# door_sensor.net
KiCad netlist of a schematic drawn in EAGLE
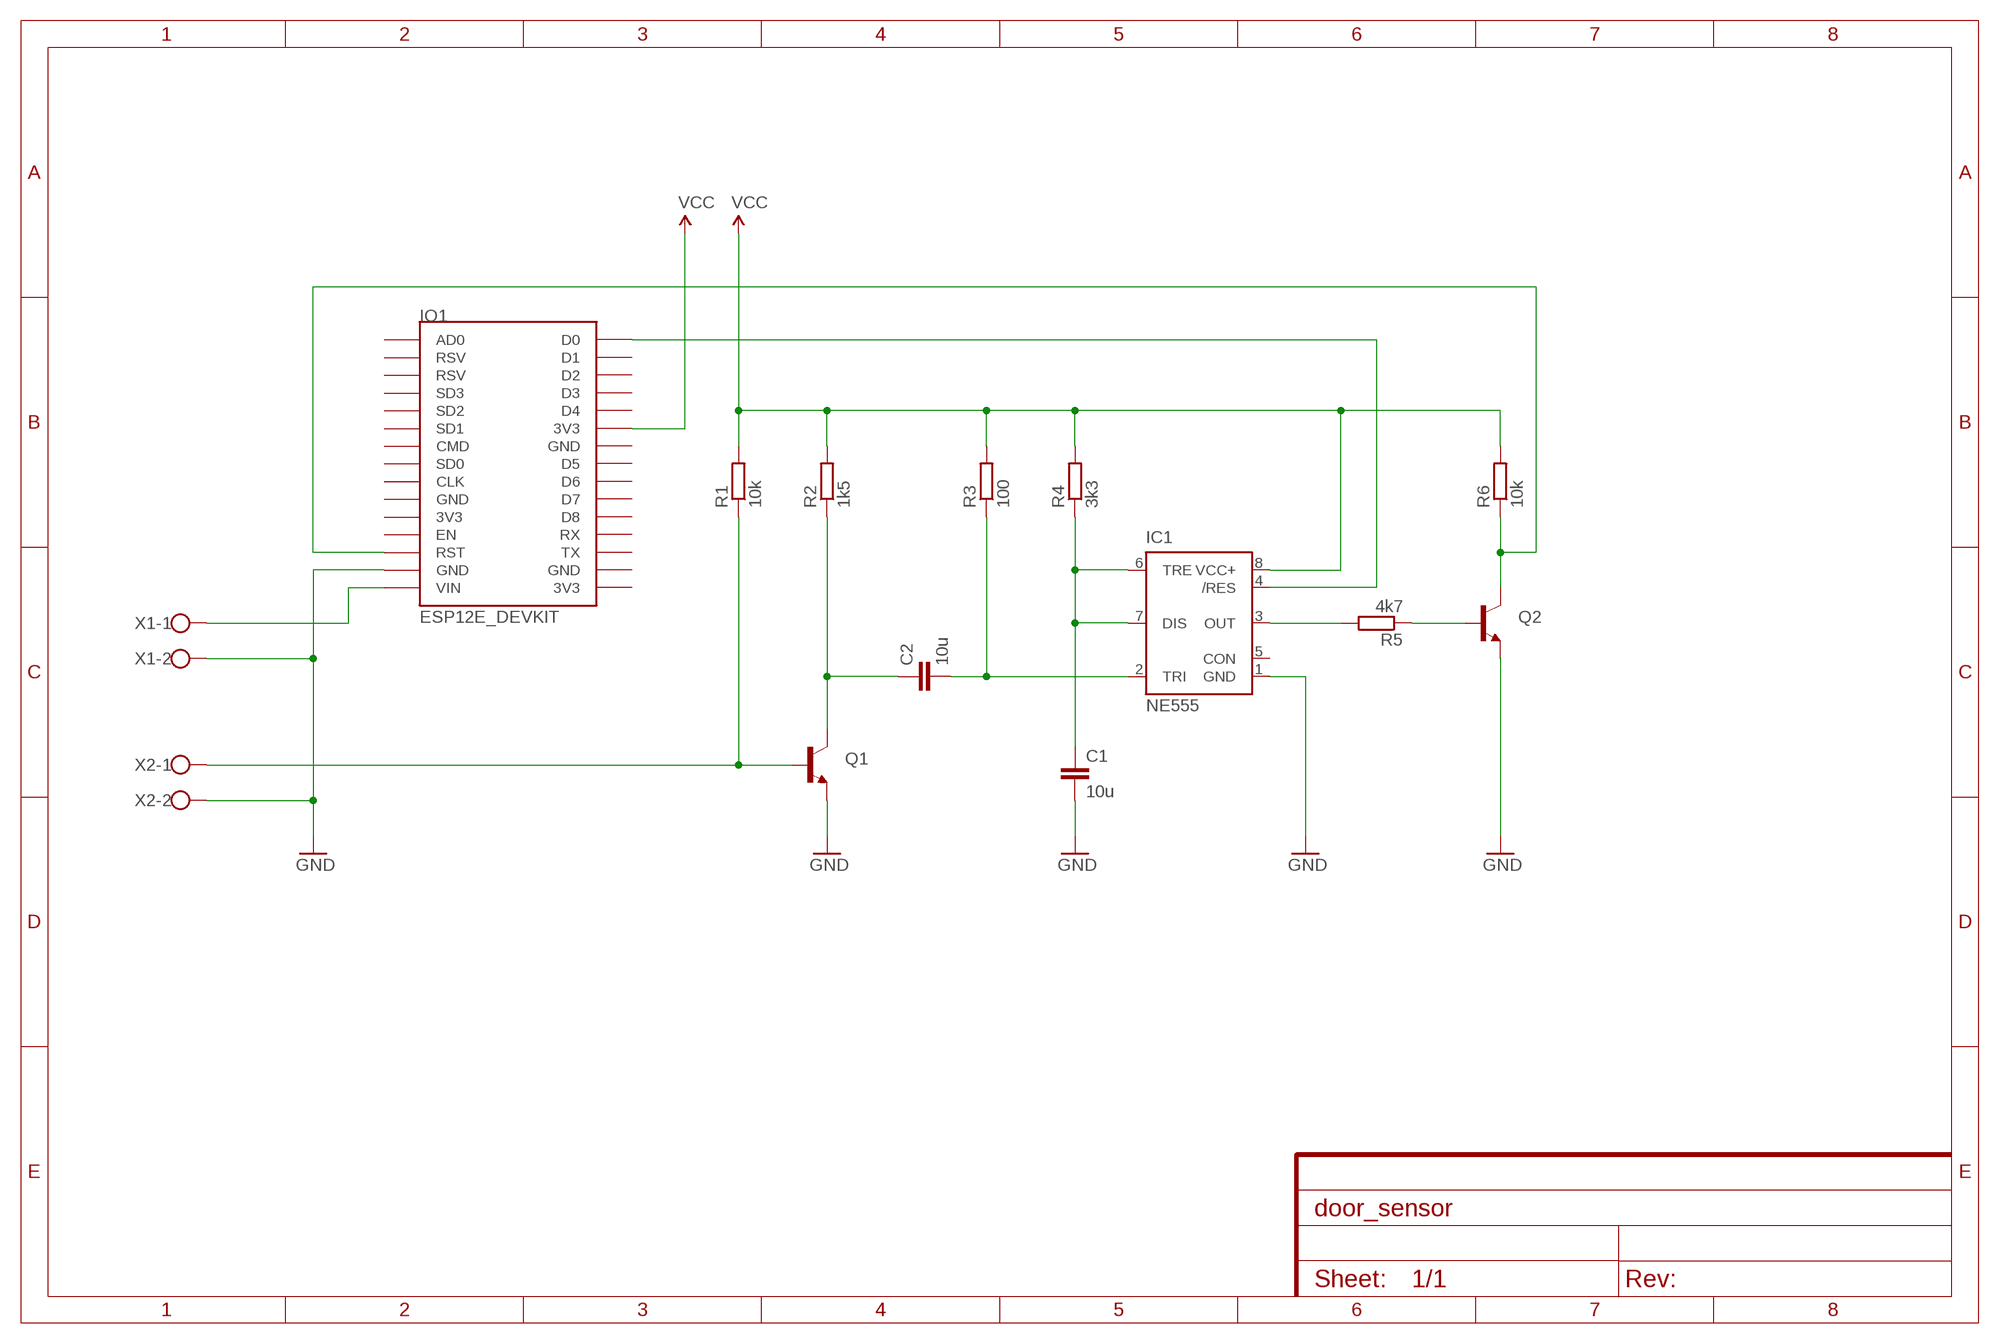
[diagram p0: schematic, sheet 1]

(export (version "E")
  (design (tool "Eeschema 10.0.6"))
  (components
    (comp (ref "C1")
      (value "10u")
      (footprint "eagle-import:C025-025X050")
      (libsource (lib "eagle-import") (part "C-EU025-025X050"))
    )
    (comp (ref "C2")
      (value "10u")
      (footprint "eagle-import:C025-025X050")
      (libsource (lib "eagle-import") (part "C-EU025-025X050"))
    )
    (comp (ref "IC1")
      (value "NE555")
      (footprint "eagle-import:DIL-08")
      (fields (field (name "MF") "Arrow Electronics") (field (name "MPN") "NE555N"))
      (libsource (lib "eagle-import") (part "NE555"))
    )
    (comp (ref "IO1")
      (value "ESP12E_DEVKIT")
      (footprint "eagle-import:ESP12E_DEVKIT")
      (libsource (lib "eagle-import") (part "ESP12E_DEVKIT"))
    )
    (comp (ref "Q1")
      (value "TRANSISTOR_NPN2N3904")
      (footprint "eagle-import:TO-92")
      (libsource (lib "eagle-import") (part "TRANSISTOR_NPN2N3904"))
    )
    (comp (ref "Q2")
      (value "TRANSISTOR_NPN2N3904")
      (footprint "eagle-import:TO-92")
      (libsource (lib "eagle-import") (part "TRANSISTOR_NPN2N3904"))
    )
    (comp (ref "R1")
      (value "10k")
      (footprint "eagle-import:0207_12")
      (libsource (lib "eagle-import") (part "R-EU_0207/12"))
    )
    (comp (ref "R2")
      (value "1k5")
      (footprint "eagle-import:0207_12")
      (libsource (lib "eagle-import") (part "R-EU_0207/12"))
    )
    (comp (ref "R3")
      (value "100")
      (footprint "eagle-import:0207_12")
      (libsource (lib "eagle-import") (part "R-EU_0207/12"))
    )
    (comp (ref "R4")
      (value "3k3")
      (footprint "eagle-import:0207_12")
      (libsource (lib "eagle-import") (part "R-EU_0207/12"))
    )
    (comp (ref "R5")
      (value "4k7")
      (footprint "eagle-import:0207_12")
      (libsource (lib "eagle-import") (part "R-EU_0207/12"))
    )
    (comp (ref "R6")
      (value "10k")
      (footprint "eagle-import:0207_12")
      (libsource (lib "eagle-import") (part "R-EU_0207/12"))
    )
    (comp (ref "X1")
      (value "AK550/2")
      (footprint "eagle-import:AK550_2")
      (libsource (lib "eagle-import") (part "AK550/2"))
    )
    (comp (ref "X2")
      (value "AK550/2")
      (footprint "eagle-import:AK550_2")
      (libsource (lib "eagle-import") (part "AK550/2"))
    )
  )
  (nets
    (net (code "1") (name "GND") (class "Default")
      (node (ref "C1") (pin "2") (pinfunction "2_2") (pintype "passive"))
      (node (ref "IC1") (pin "1") (pinfunction "GND_1") (pintype "power_in"))
      (node (ref "IO1") (pin "GND@1") (pinfunction "GND_GND@1") (pintype "bidirectional"))
      (node (ref "Q1") (pin "1") (pinfunction "E_1") (pintype "passive"))
      (node (ref "Q2") (pin "1") (pinfunction "E_1") (pintype "passive"))
      (node (ref "X1") (pin "2") (pinfunction "KL_2") (pintype "passive"))
      (node (ref "X2") (pin "2") (pinfunction "KL_2") (pintype "passive"))
    )
    (net (code "2") (name "Net-(IC1-DIS)") (class "Default")
      (node (ref "C1") (pin "1") (pinfunction "1_1") (pintype "passive"))
      (node (ref "IC1") (pin "6") (pinfunction "TRE_6") (pintype "input"))
      (node (ref "IC1") (pin "7") (pinfunction "DIS_7") (pintype "input"))
      (node (ref "R4") (pin "1") (pinfunction "1_1") (pintype "passive"))
    )
    (net (code "3") (name "Net-(IC1-OUT)") (class "Default")
      (node (ref "IC1") (pin "3") (pinfunction "OUT_3") (pintype "output"))
      (node (ref "R5") (pin "2") (pinfunction "2_2") (pintype "passive"))
    )
    (net (code "4") (name "Net-(IC1-TRI)") (class "Default")
      (node (ref "C2") (pin "2") (pinfunction "2_2") (pintype "passive"))
      (node (ref "IC1") (pin "2") (pinfunction "TRI_2") (pintype "input"))
      (node (ref "R3") (pin "1") (pinfunction "1_1") (pintype "passive"))
    )
    (net (code "5") (name "Net-(IC1-{slash}RES)") (class "Default")
      (node (ref "IC1") (pin "4") (pinfunction "/RES_4") (pintype "input"))
      (node (ref "IO1") (pin "D0") (pinfunction "D0_D0") (pintype "bidirectional"))
    )
    (net (code "6") (name "Net-(Q1-B)") (class "Default")
      (node (ref "Q1") (pin "2") (pinfunction "B_2") (pintype "passive"))
      (node (ref "R1") (pin "1") (pinfunction "1_1") (pintype "passive"))
      (node (ref "X2") (pin "1") (pinfunction "KL_1") (pintype "passive"))
    )
    (net (code "7") (name "Net-(Q1-C)") (class "Default")
      (node (ref "C2") (pin "1") (pinfunction "1_1") (pintype "passive"))
      (node (ref "Q1") (pin "3") (pinfunction "C_3") (pintype "passive"))
      (node (ref "R2") (pin "1") (pinfunction "1_1") (pintype "passive"))
    )
    (net (code "8") (name "Net-(Q2-B)") (class "Default")
      (node (ref "Q2") (pin "2") (pinfunction "B_2") (pintype "passive"))
      (node (ref "R5") (pin "1") (pinfunction "1_1") (pintype "passive"))
    )
    (net (code "9") (name "Net-(Q2-C)") (class "Default")
      (node (ref "IO1") (pin "RST") (pinfunction "RST_RST") (pintype "bidirectional"))
      (node (ref "Q2") (pin "3") (pinfunction "C_3") (pintype "passive"))
      (node (ref "R6") (pin "1") (pinfunction "1_1") (pintype "passive"))
    )
    (net (code "10") (name "Net-(X1A-KL)") (class "Default")
      (node (ref "IO1") (pin "VIN") (pinfunction "VIN_VIN") (pintype "bidirectional"))
      (node (ref "X1") (pin "1") (pinfunction "KL_1") (pintype "passive"))
    )
    (net (code "11") (name "VCC") (class "Default")
      (node (ref "IC1") (pin "8") (pinfunction "VCC+_8") (pintype "power_in"))
      (node (ref "IO1") (pin "3V3@1") (pinfunction "3V3_3V3@1") (pintype "bidirectional"))
      (node (ref "R1") (pin "2") (pinfunction "2_2") (pintype "passive"))
      (node (ref "R2") (pin "2") (pinfunction "2_2") (pintype "passive"))
      (node (ref "R3") (pin "2") (pinfunction "2_2") (pintype "passive"))
      (node (ref "R4") (pin "2") (pinfunction "2_2") (pintype "passive"))
      (node (ref "R6") (pin "2") (pinfunction "2_2") (pintype "passive"))
    )
    (net (code "12") (name "unconnected-(IC1-CON-Pad5)") (class "Default")
      (node (ref "IC1") (pin "5") (pinfunction "CON_5") (pintype "input"))
    )
    (net (code "13") (name "unconnected-(IO1-3V3-Pad3V3@0)") (class "Default")
      (node (ref "IO1") (pin "3V3@0") (pinfunction "3V3_3V3@0") (pintype "bidirectional"))
    )
    (net (code "14") (name "unconnected-(IO1-3V3-Pad3V3@2)") (class "Default")
      (node (ref "IO1") (pin "3V3@2") (pinfunction "3V3_3V3@2") (pintype "bidirectional"))
    )
    (net (code "15") (name "unconnected-(IO1-GND-PadGND@0)") (class "Default")
      (node (ref "IO1") (pin "GND@0") (pinfunction "GND_GND@0") (pintype "bidirectional"))
    )
    (net (code "16") (name "unconnected-(IO1-GND-PadGND@2)") (class "Default")
      (node (ref "IO1") (pin "GND@2") (pinfunction "GND_GND@2") (pintype "bidirectional"))
    )
    (net (code "17") (name "unconnected-(IO1-GND-PadGND@3)") (class "Default")
      (node (ref "IO1") (pin "GND@3") (pinfunction "GND_GND@3") (pintype "bidirectional"))
    )
    (net (code "18") (name "unconnected-(IO1-PadAD0)") (class "Default")
      (node (ref "IO1") (pin "AD0") (pinfunction "AD0_AD0") (pintype "bidirectional"))
    )
    (net (code "19") (name "unconnected-(IO1-PadCLK)") (class "Default")
      (node (ref "IO1") (pin "CLK") (pinfunction "CLK_CLK") (pintype "bidirectional"))
    )
    (net (code "20") (name "unconnected-(IO1-PadCMD)") (class "Default")
      (node (ref "IO1") (pin "CMD") (pinfunction "CMD_CMD") (pintype "bidirectional"))
    )
    (net (code "21") (name "unconnected-(IO1-PadD1)") (class "Default")
      (node (ref "IO1") (pin "D1") (pinfunction "D1_D1") (pintype "bidirectional"))
    )
    (net (code "22") (name "unconnected-(IO1-PadD2)") (class "Default")
      (node (ref "IO1") (pin "D2") (pinfunction "D2_D2") (pintype "bidirectional"))
    )
    (net (code "23") (name "unconnected-(IO1-PadD3)") (class "Default")
      (node (ref "IO1") (pin "D3") (pinfunction "D3_D3") (pintype "bidirectional"))
    )
    (net (code "24") (name "unconnected-(IO1-PadD4)") (class "Default")
      (node (ref "IO1") (pin "D4") (pinfunction "D4_D4") (pintype "bidirectional"))
    )
    (net (code "25") (name "unconnected-(IO1-PadD5)") (class "Default")
      (node (ref "IO1") (pin "D5") (pinfunction "D5_D5") (pintype "bidirectional"))
    )
    (net (code "26") (name "unconnected-(IO1-PadD6)") (class "Default")
      (node (ref "IO1") (pin "D6") (pinfunction "D6_D6") (pintype "bidirectional"))
    )
    (net (code "27") (name "unconnected-(IO1-PadD7)") (class "Default")
      (node (ref "IO1") (pin "D7") (pinfunction "D7_D7") (pintype "bidirectional"))
    )
    (net (code "28") (name "unconnected-(IO1-PadD8)") (class "Default")
      (node (ref "IO1") (pin "D8") (pinfunction "D8_D8") (pintype "bidirectional"))
    )
    (net (code "29") (name "unconnected-(IO1-PadEN)") (class "Default")
      (node (ref "IO1") (pin "EN") (pinfunction "EN_EN") (pintype "bidirectional"))
    )
    (net (code "30") (name "unconnected-(IO1-PadRX)") (class "Default")
      (node (ref "IO1") (pin "RX") (pinfunction "RX_RX") (pintype "bidirectional"))
    )
    (net (code "31") (name "unconnected-(IO1-PadSD0)") (class "Default")
      (node (ref "IO1") (pin "SD0") (pinfunction "SD0_SD0") (pintype "bidirectional"))
    )
    (net (code "32") (name "unconnected-(IO1-PadSD1)") (class "Default")
      (node (ref "IO1") (pin "SD1") (pinfunction "SD1_SD1") (pintype "bidirectional"))
    )
    (net (code "33") (name "unconnected-(IO1-PadSD2)") (class "Default")
      (node (ref "IO1") (pin "SD2") (pinfunction "SD2_SD2") (pintype "bidirectional"))
    )
    (net (code "34") (name "unconnected-(IO1-PadSD3)") (class "Default")
      (node (ref "IO1") (pin "SD3") (pinfunction "SD3_SD3") (pintype "bidirectional"))
    )
    (net (code "35") (name "unconnected-(IO1-PadTX)") (class "Default")
      (node (ref "IO1") (pin "TX") (pinfunction "TX_TX") (pintype "bidirectional"))
    )
    (net (code "36") (name "unconnected-(IO1-RSV-PadRSV@0)") (class "Default")
      (node (ref "IO1") (pin "RSV@0") (pinfunction "RSV_RSV@0") (pintype "bidirectional"))
    )
    (net (code "37") (name "unconnected-(IO1-RSV-PadRSV@1)") (class "Default")
      (node (ref "IO1") (pin "RSV@1") (pinfunction "RSV_RSV@1") (pintype "bidirectional"))
    )
  )
)
